# Current_Sensing.net
KiCad netlist of a schematic drawn in Altium Designer
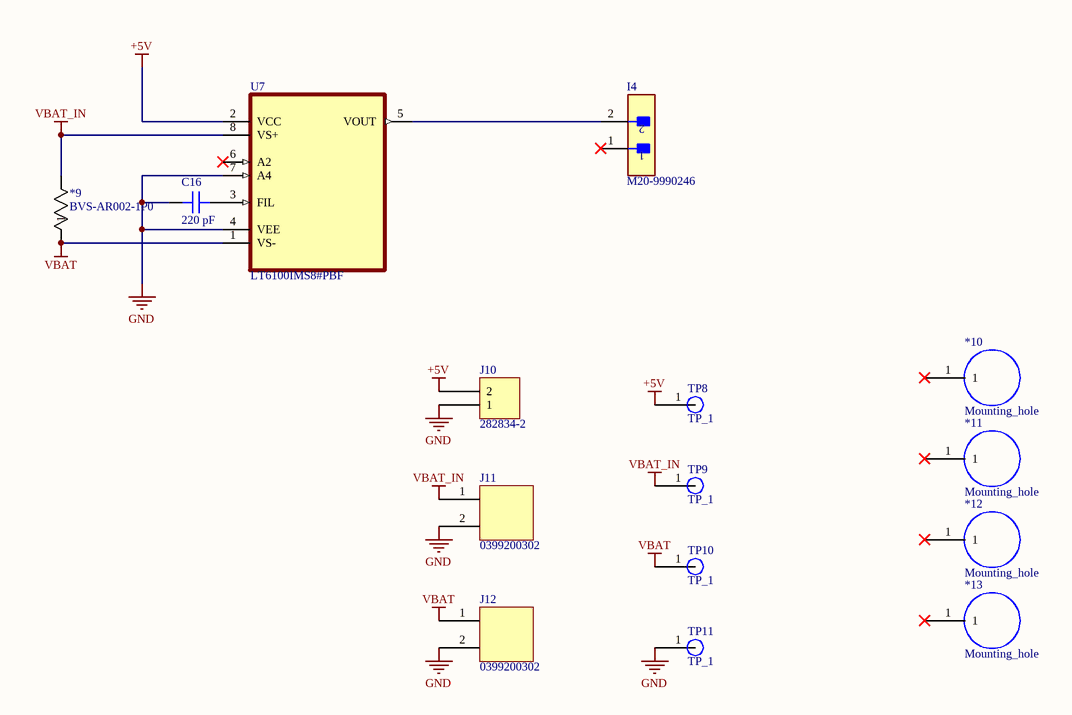
[diagram p0: Current Sensing.SchDoc]

(export (version "E")
  (design (tool "Eeschema 10.0.6"))
  (components
    (comp (ref "*9")
      (value "BVS-AR002-1P0")
      (footprint "BVS-R002-1P0")
      (libsource (lib "Seaglider_Power_board_Schematic_Library") (part "BVS-AR002-1P0"))
    )
    (comp (ref "*10")
      (value "Mounting_hole")
      (footprint "Mounting_Hole")
      (libsource (lib "Seaglider_Power_board_Schematic_Library") (part "Mounting_hole"))
    )
    (comp (ref "*11")
      (value "Mounting_hole")
      (footprint "Mounting_Hole")
      (libsource (lib "Seaglider_Power_board_Schematic_Library") (part "Mounting_hole"))
    )
    (comp (ref "*12")
      (value "Mounting_hole")
      (footprint "Mounting_Hole")
      (libsource (lib "Seaglider_Power_board_Schematic_Library") (part "Mounting_hole"))
    )
    (comp (ref "*13")
      (value "Mounting_hole")
      (footprint "Mounting_Hole")
      (libsource (lib "Seaglider_Power_board_Schematic_Library") (part "Mounting_hole"))
    )
    (comp (ref "C16")
      (value "220 pF")
      (footprint "CAP 0402_1005")
      (description "CAP CER 220PF 50V CH 0402")
      (fields (field (name "PART NUMBER") "UMK105CH221JVHF") (field (name "MANUFACTURER") "Taiyo Yuden"))
      (libsource (lib "Celestial Altium Library - altium_library (2)") (part "Capacitor"))
    )
    (comp (ref "I4")
      (value "M20-9990246")
      (footprint "FP-M20-9990246-MFG")
      (description "CONN HEADER VERT 2POS 2.54MM")
      (fields
        (field (name "OCTOPART") "https://octopart.com/m20-9990246-harwin-2590635")
        (field (name "MANUFACTURER") "Harwin")
      )
      (libsource (lib "Altium Content Vault") (part "3bc925449376181038e59eaffc5286c"))
    )
    (comp (ref "J10")
      (value "282834-2")
      (footprint "TE 282834-2")
      (description "TERM BLK 2P SIDE ENT 2.54MM PCB")
      (fields (field (name "MANUFACTURER") "TE Connectivity AMP Connectors") (field (name "VOLTAGE") "150V"))
      (libsource (lib "Celestial Altium Library - altium_library (2)") (part "2 Pin"))
    )
    (comp (ref "J11")
      (value "0399200302")
      (footprint "0399200302")
      (libsource (lib "Seaglider_Power_board_Schematic_Library") (part "0399200302"))
    )
    (comp (ref "J12")
      (value "0399200302")
      (footprint "0399200302")
      (libsource (lib "Seaglider_Power_board_Schematic_Library") (part "0399200302"))
    )
    (comp (ref "TP8")
      (value "TP_1")
      (footprint "Test_point1")
      (libsource (lib "Seaglider_Power_board_Schematic_Library") (part "Test_point1"))
    )
    (comp (ref "TP9")
      (value "TP_1")
      (footprint "Test_point1")
      (libsource (lib "Seaglider_Power_board_Schematic_Library") (part "Test_point1"))
    )
    (comp (ref "TP10")
      (value "TP_1")
      (footprint "Test_point1")
      (libsource (lib "Seaglider_Power_board_Schematic_Library") (part "Test_point1"))
    )
    (comp (ref "TP11")
      (value "TP_1")
      (footprint "Test_point1")
      (libsource (lib "Seaglider_Power_board_Schematic_Library") (part "Test_point1"))
    )
    (comp (ref "U7")
      (value "LT6100IMS8#PBF")
      (footprint "SOP65P490X110-8N")
      (description "Precision, Gain Selectable High Side Current Sense Amplifier")
      (fields (field (name "MF") "Analog Devices"))
      (libsource (lib "Americas- Environmental Engineering Club- University of Victoria") (part "LT6100IMS8#PBF"))
    )
  )
  (nets
    (net (code "1") (name "+5V") (class "Default")
      (node (ref "J10") (pin "2") (pinfunction "2_2") (pintype "passive"))
      (node (ref "TP8") (pin "1") (pintype "passive"))
      (node (ref "U7") (pin "2") (pinfunction "VCC_2") (pintype "power_in"))
    )
    (net (code "2") (name "GND") (class "Default")
      (node (ref "C16") (pin "1") (pinfunction "1_1") (pintype "passive"))
      (node (ref "J10") (pin "1") (pinfunction "1_1") (pintype "passive"))
      (node (ref "J11") (pin "2") (pintype "passive"))
      (node (ref "J12") (pin "2") (pintype "passive"))
      (node (ref "TP11") (pin "1") (pintype "passive"))
      (node (ref "U7") (pin "4") (pinfunction "VEE_4") (pintype "power_in"))
      (node (ref "U7") (pin "7") (pinfunction "A4_7") (pintype "input"))
    )
    (net (code "3") (name "Net-(U7-FIL)") (class "Default")
      (node (ref "C16") (pin "2") (pinfunction "2_2") (pintype "passive"))
      (node (ref "U7") (pin "3") (pinfunction "FIL_3") (pintype "input"))
    )
    (net (code "4") (name "Net-(U7-VOUT)") (class "Default")
      (node (ref "I4") (pin "2") (pinfunction "2_2") (pintype "passive"))
      (node (ref "U7") (pin "5") (pinfunction "VOUT_5") (pintype "output"))
    )
    (net (code "5") (name "VBAT") (class "Default")
      (node (ref "*9") (pin "1") (pinfunction "1_1") (pintype "passive"))
      (node (ref "J12") (pin "1") (pintype "passive"))
      (node (ref "TP10") (pin "1") (pintype "passive"))
      (node (ref "U7") (pin "1") (pinfunction "VS-_1") (pintype "power_in"))
    )
    (net (code "6") (name "VBAT_IN") (class "Default")
      (node (ref "*9") (pin "2") (pinfunction "2_2") (pintype "passive"))
      (node (ref "J11") (pin "1") (pintype "passive"))
      (node (ref "TP9") (pin "1") (pintype "passive"))
      (node (ref "U7") (pin "8") (pinfunction "VS+_8") (pintype "power_in"))
    )
    (net (code "7") (name "unconnected-(*10-Pad1)") (class "Default")
      (node (ref "*10") (pin "1") (pinfunction "1_1") (pintype "passive+no_connect"))
    )
    (net (code "8") (name "unconnected-(*11-Pad1)") (class "Default")
      (node (ref "*11") (pin "1") (pinfunction "1_1") (pintype "passive+no_connect"))
    )
    (net (code "9") (name "unconnected-(*12-Pad1)") (class "Default")
      (node (ref "*12") (pin "1") (pinfunction "1_1") (pintype "passive+no_connect"))
    )
    (net (code "10") (name "unconnected-(*13-Pad1)") (class "Default")
      (node (ref "*13") (pin "1") (pinfunction "1_1") (pintype "passive+no_connect"))
    )
    (net (code "11") (name "unconnected-(I4-Pad1)") (class "Default")
      (node (ref "I4") (pin "1") (pinfunction "1_1") (pintype "passive+no_connect"))
    )
    (net (code "12") (name "unconnected-(U7-A2-Pad6)") (class "Default")
      (node (ref "U7") (pin "6") (pinfunction "A2_6") (pintype "input+no_connect"))
    )
  )
)
